# -STM32F1-4_0.net
KiCad netlist of a schematic drawn in EasyEDA Pro
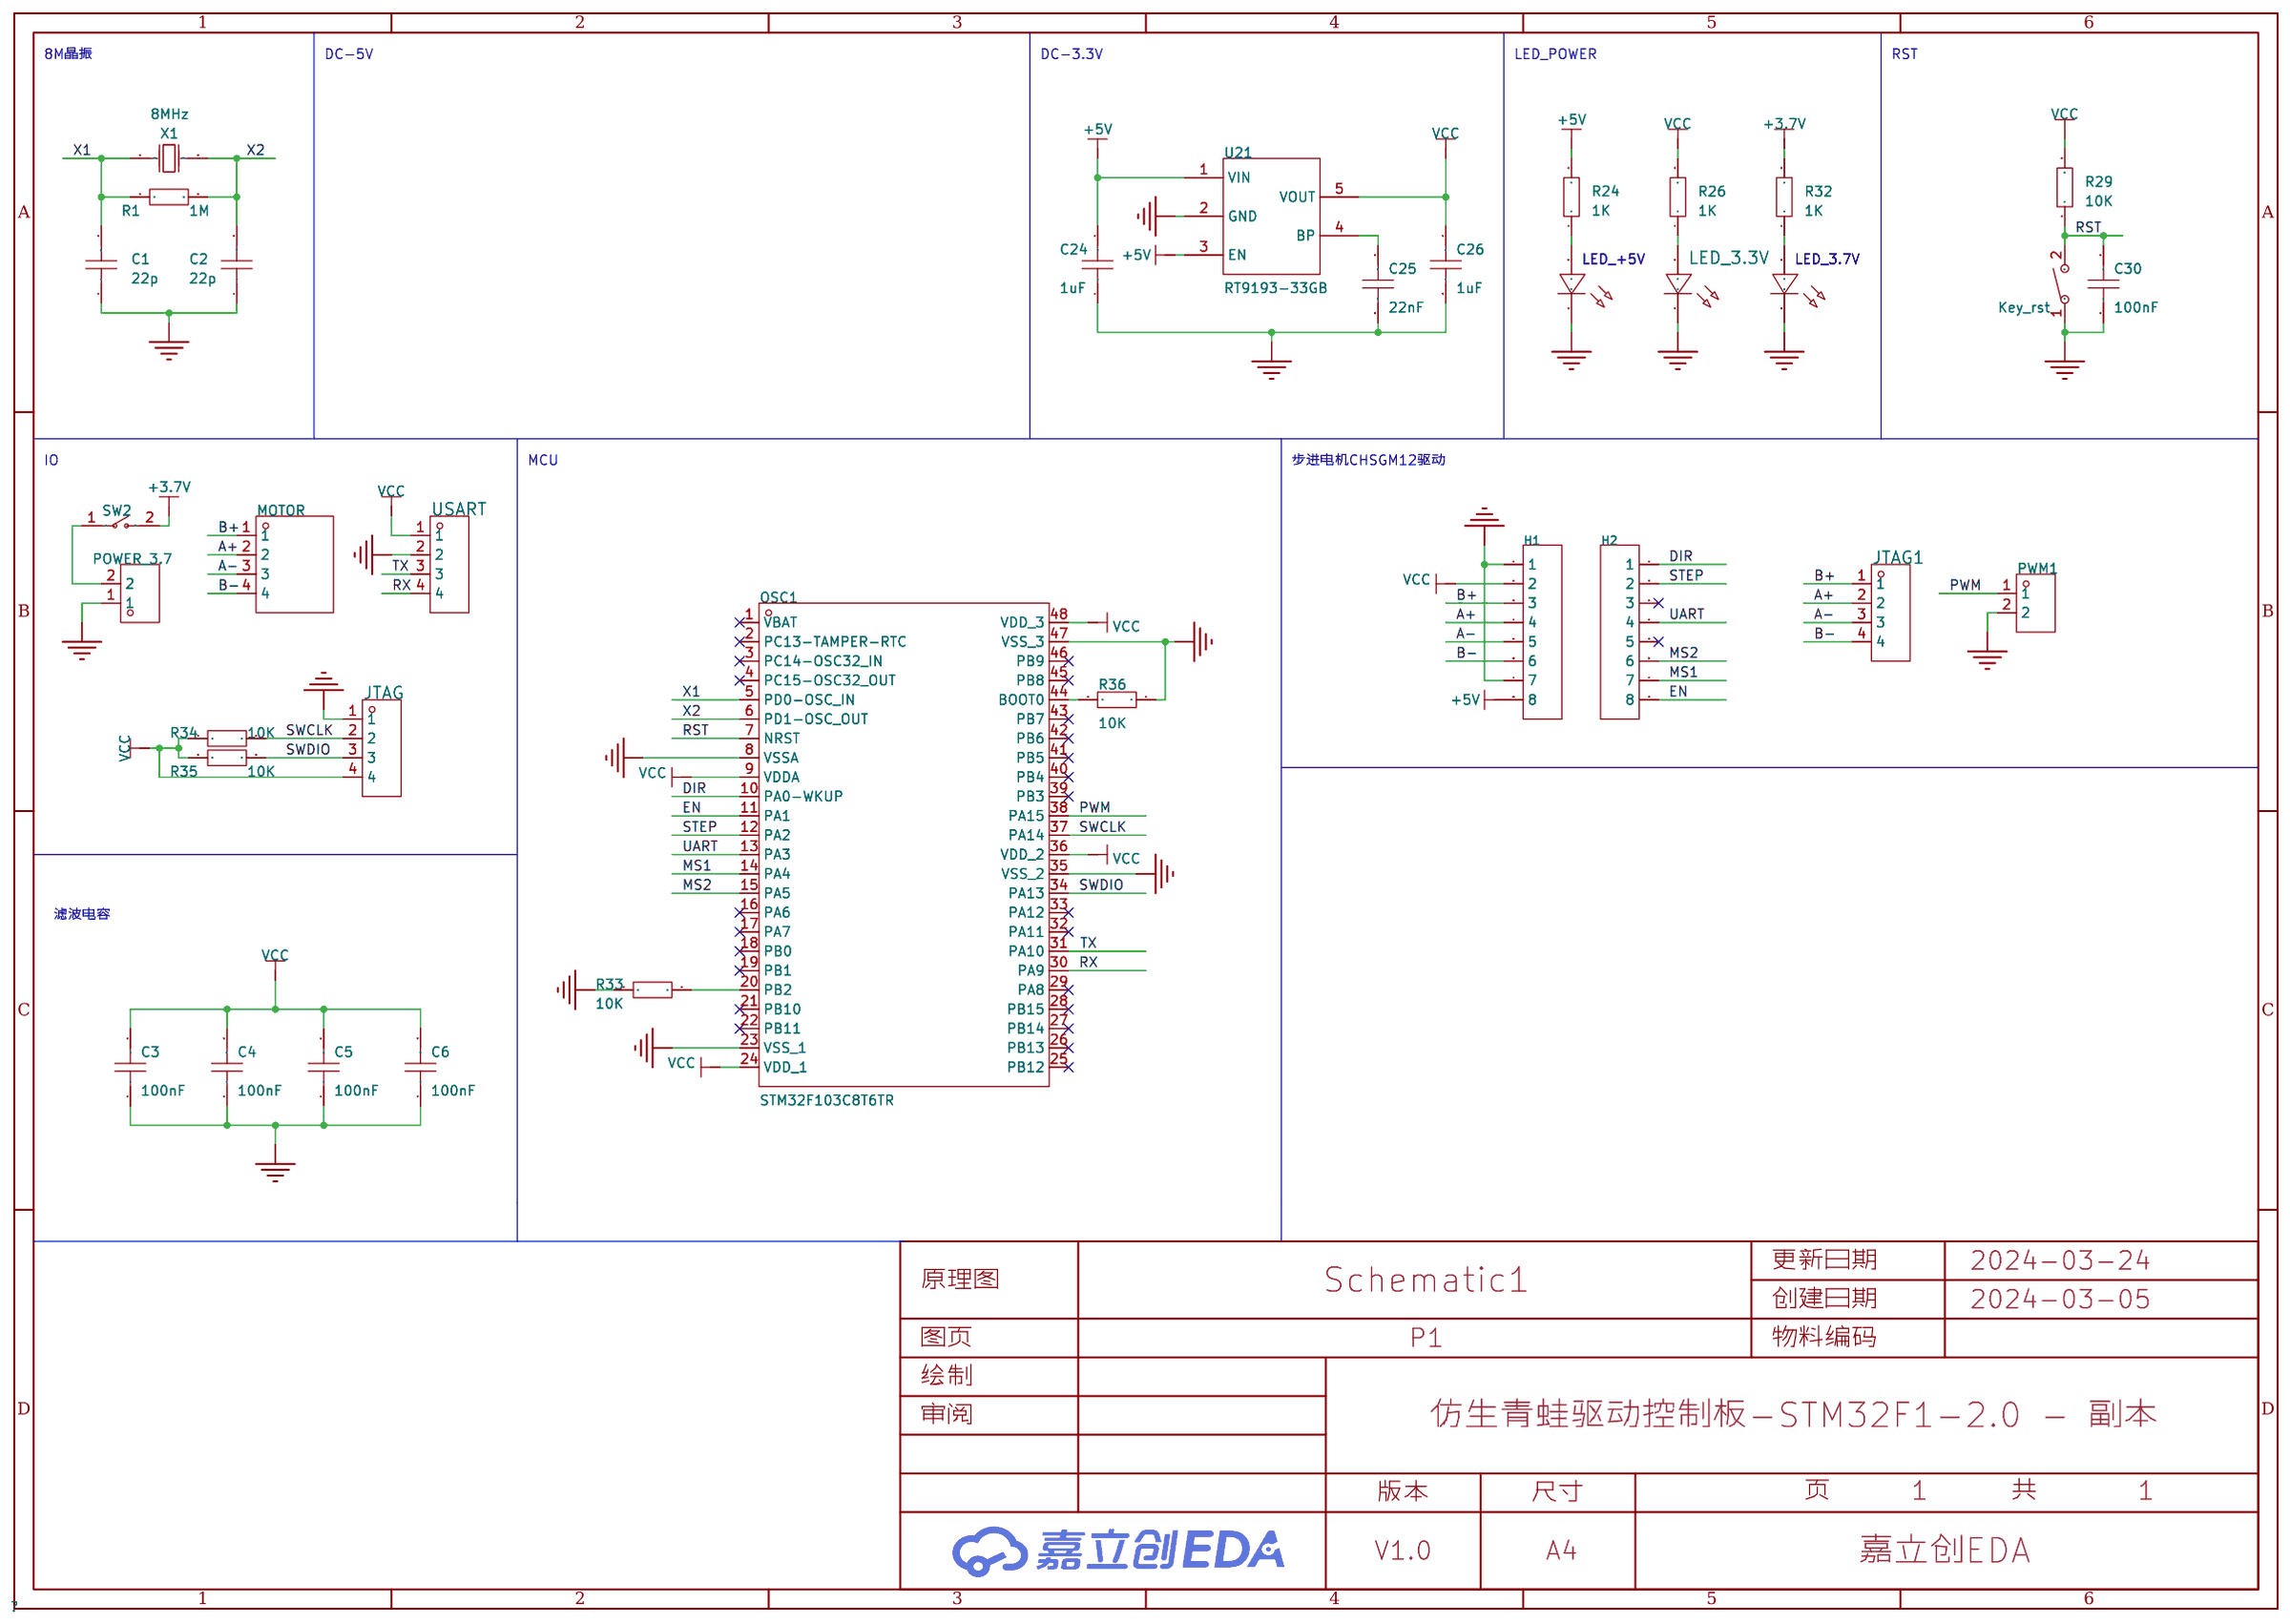
[diagram p0: schematic sheet]

(export (version "E")
  (design (tool "Eeschema 10.0.6"))
  (components
    (comp (ref "C1")
      (value "22p")
      (footprint "easyedapro:c0603")
      (libsource (lib "easyedapro") (part "CapAcitance"))
    )
    (comp (ref "C2")
      (value "22p")
      (footprint "easyedapro:c0603")
      (libsource (lib "easyedapro") (part "CapAcitance"))
    )
    (comp (ref "C3")
      (value "100nF")
      (footprint "easyedapro:c0603")
      (libsource (lib "easyedapro") (part "CapAcitance"))
    )
    (comp (ref "C4")
      (value "100nF")
      (footprint "easyedapro:c0603")
      (libsource (lib "easyedapro") (part "CapAcitance"))
    )
    (comp (ref "C5")
      (value "100nF")
      (footprint "easyedapro:c0603")
      (libsource (lib "easyedapro") (part "CapAcitance"))
    )
    (comp (ref "C6")
      (value "100nF")
      (footprint "easyedapro:c0603")
      (libsource (lib "easyedapro") (part "CapAcitance"))
    )
    (comp (ref "C24")
      (value "1uF")
      (footprint "easyedapro:c0603")
      (libsource (lib "easyedapro") (part "CapAcitance"))
    )
    (comp (ref "C25")
      (value "22nF")
      (footprint "easyedapro:c0603")
      (libsource (lib "easyedapro") (part "CapAcitance"))
    )
    (comp (ref "C26")
      (value "1uF")
      (footprint "easyedapro:c0603")
      (libsource (lib "easyedapro") (part "CapAcitance"))
    )
    (comp (ref "C30")
      (value "100nF")
      (footprint "easyedapro:c0603")
      (libsource (lib "easyedapro") (part "CapAcitance"))
    )
    (comp (ref "H1")
      (value "~")
      (footprint "easyedapro:HDR-TH_8P-P2.54-V-F-1")
      (libsource (lib "easyedapro") (part "Header-Female-2.54_1x8"))
    )
    (comp (ref "H2")
      (value "~")
      (footprint "easyedapro:HDR-TH_8P-P2.54-V-F-1")
      (libsource (lib "easyedapro") (part "Header-Female-2.54_1x8"))
    )
    (comp (ref "JTAG")
      (value "~")
      (footprint "easyedapro:HDR-TH_4P-P2.54-V-F")
      (libsource (lib "easyedapro") (part "2.54-1*4P母"))
    )
    (comp (ref "JTAG1")
      (value "~")
      (footprint "easyedapro:HDR-TH_4P-P2.54-V-F")
      (libsource (lib "easyedapro") (part "2.54-1*4P母"))
    )
    (comp (ref "Key_rst")
      (value "TS-1092S-B3D2-G")
      (footprint "easyedapro:SW-SMD_L6.1-W3.6-LS7.9")
      (description "电路结构:单刀单掷;按钮形状:矩形按钮;作用力:250gf;安装方式:立贴;开关长度:6.1mm;开关宽度:3.6mm;开关高度:2.5mm;带支架:不带;机械寿命:-;")
      (fields (field (name "Manufacturer") "Yuandi(元迪)"))
      (libsource (lib "easyedapro") (part "TS-1092S-B3D2-G"))
    )
    (comp (ref "LED_+5V")
      (value "~")
      (footprint "easyedapro:LED_0603")
      (libsource (lib "easyedapro") (part "LED_G"))
    )
    (comp (ref "LED_3.3V")
      (value "~")
      (footprint "easyedapro:LED_0402")
      (libsource (lib "easyedapro") (part "LED_R"))
    )
    (comp (ref "LED_3.7V")
      (value "~")
      (footprint "easyedapro:LED_0402")
      (libsource (lib "easyedapro") (part "LED_B"))
    )
    (comp (ref "MOTOR")
      (value "DF13-4P-1.25DSA")
      (footprint "easyedapro:CONN-TH_DF13-4P-1.25DSA")
      (description "插针结构:1x4P;间距:1.25mm;安装方式:-;参考系列:-;总PIN数:4P;排数:1;每排PIN数:4;行距:-;触头材质:黄铜;")
      (fields (field (name "Manufacturer") "HRS(广濑)"))
      (libsource (lib "easyedapro") (part "DF13-4P-1.25DSA"))
    )
    (comp (ref "OSC1")
      (value "STM32F103C8T6TR")
      (footprint "easyedapro:LQFP-48_L7.0-W7.0-P0.50-LS9.0-BL")
      (description "CPU内核:CM3;程序存储容量:64KB;RAM总容量:20KB;GPIO端口数量:37;工作电压范围:2V~3.6V;CPU最大主频:72MHz;程序存储器类型:-;")
      (fields (field (name "Manufacturer") "ST(意法半导体)"))
      (libsource (lib "easyedapro") (part "STM32F103C8T6TR"))
    )
    (comp (ref "POWER_3.7")
      (value "ZX-XH2.54-2PZZ")
      (footprint "easyedapro:CONN-TH_2P-P2.50_HX25003-2A")
      (fields (field (name "Manufacturer") "Megastar(兆星)"))
      (libsource (lib "easyedapro") (part "ZX-XH2.54-2PZZ"))
    )
    (comp (ref "PWM1")
      (value "ZX-XH2.54-2PZZ")
      (footprint "easyedapro:CONN-TH_2P-P2.50_HX25003-2A")
      (fields (field (name "Manufacturer") "Megastar(兆星)"))
      (libsource (lib "easyedapro") (part "ZX-XH2.54-2PZZ"))
    )
    (comp (ref "R1") (value "1M") (footprint "easyedapro:r0603") (libsource (lib "easyedapro") (part "电阻")))
    (comp (ref "R24") (value "1K") (footprint "easyedapro:R0805") (libsource (lib "easyedapro") (part "电阻")))
    (comp (ref "R26") (value "1K") (footprint "easyedapro:r0603") (libsource (lib "easyedapro") (part "电阻")))
    (comp (ref "R29") (value "10K") (footprint "easyedapro:r0603") (libsource (lib "easyedapro") (part "电阻")))
    (comp (ref "R32") (value "1K") (footprint "easyedapro:r0603") (libsource (lib "easyedapro") (part "电阻")))
    (comp (ref "R33") (value "10K") (footprint "easyedapro:r0603") (libsource (lib "easyedapro") (part "电阻")))
    (comp (ref "R34") (value "10K") (footprint "easyedapro:r0603") (libsource (lib "easyedapro") (part "电阻")))
    (comp (ref "R35") (value "10K") (footprint "easyedapro:r0603") (libsource (lib "easyedapro") (part "电阻")))
    (comp (ref "R36") (value "10K") (footprint "easyedapro:r0603") (libsource (lib "easyedapro") (part "电阻")))
    (comp (ref "SW2")
      (value "KCD11-2P-R")
      (footprint "easyedapro:SW-TH_2P-L15.0-W10.5-P5.00_KCD11-2P-R")
      (description "带灯:无;引脚样式:焊片;额定电流:3A;额定电压(AC):250V;额定电压(DC):-;电路结构:单刀单掷;机械寿命:1万次;")
      (fields (field (name "Manufacturer") "SHOU HAN(首韩)"))
      (libsource (lib "easyedapro") (part "KCD11-2P-R"))
    )
    (comp (ref "U21")
      (value "RT9193-33GB")
      (footprint "easyedapro:SOT-23-5_L3.0-W1.7-P0.95-LS2.8-BL")
      (description "输出类型:固定;最大输入电压:5.5V;输出电压:3.3V;最大输出电流:300mA;电源纹波抑制比(PSRR):70dB;输出极性:正极;")
      (fields (field (name "Manufacturer") "RICHTEK(立锜)"))
      (libsource (lib "easyedapro") (part "RT9193-33GB"))
    )
    (comp (ref "USART")
      (value "~")
      (footprint "easyedapro:HDR-TH_4P-P2.54-V-F")
      (libsource (lib "easyedapro") (part "2.54-1*4P母"))
    )
    (comp (ref "X1")
      (value "8MHz")
      (footprint "easyedapro:CRYSTAL-SMD_L5.0-W3.2")
      (description "晶振类型:贴片晶振;频率:8MHz;常温频差:±10ppm;外接负载电容:20pF;频率稳定度(全温):±50ppm;")
      (fields (field (name "Manufacturer Part") "X50328MSB2GI") (field (name "Manufacturer") "YXC(扬兴晶振)"))
      (libsource (lib "easyedapro") (part "X50328MSB2GI"))
    )
  )
  (nets
    (net (code "1") (name "+3.7V") (class "Default")
      (node (ref "R32") (pin "2") (pinfunction "2_2") (pintype "input"))
      (node (ref "SW2") (pin "2") (pinfunction "2_2") (pintype "unspecified"))
    )
    (net (code "2") (name "+5V") (class "Default")
      (node (ref "C24") (pin "2") (pinfunction "2_2") (pintype "input"))
      (node (ref "H1") (pin "8") (pinfunction "8_8") (pintype "input"))
      (node (ref "R24") (pin "2") (pinfunction "2_2") (pintype "input"))
      (node (ref "U21") (pin "1") (pinfunction "VIN_1") (pintype "unspecified"))
      (node (ref "U21") (pin "3") (pinfunction "EN_3") (pintype "unspecified"))
    )
    (net (code "3") (name "/A+") (class "Default")
      (node (ref "H1") (pin "4") (pinfunction "4_4") (pintype "input"))
      (node (ref "JTAG1") (pin "2") (pinfunction "2_2") (pintype "input"))
      (node (ref "MOTOR") (pin "2") (pinfunction "2_2") (pintype "unspecified"))
    )
    (net (code "4") (name "/A-") (class "Default")
      (node (ref "H1") (pin "5") (pinfunction "5_5") (pintype "input"))
      (node (ref "JTAG1") (pin "3") (pinfunction "3_3") (pintype "input"))
      (node (ref "MOTOR") (pin "3") (pinfunction "3_3") (pintype "unspecified"))
    )
    (net (code "5") (name "/B+") (class "Default")
      (node (ref "H1") (pin "3") (pinfunction "3_3") (pintype "input"))
      (node (ref "JTAG1") (pin "1") (pinfunction "1_1") (pintype "input"))
      (node (ref "MOTOR") (pin "1") (pinfunction "1_1") (pintype "unspecified"))
    )
    (net (code "6") (name "/B-") (class "Default")
      (node (ref "H1") (pin "6") (pinfunction "6_6") (pintype "input"))
      (node (ref "JTAG1") (pin "4") (pinfunction "4_4") (pintype "input"))
      (node (ref "MOTOR") (pin "4") (pinfunction "4_4") (pintype "unspecified"))
    )
    (net (code "7") (name "/DIR") (class "Default")
      (node (ref "H2") (pin "1") (pinfunction "1_1") (pintype "input"))
      (node (ref "OSC1") (pin "10") (pinfunction "PA0-WKUP_10") (pintype "unspecified"))
    )
    (net (code "8") (name "/EN") (class "Default")
      (node (ref "H2") (pin "8") (pinfunction "8_8") (pintype "input"))
      (node (ref "OSC1") (pin "11") (pinfunction "PA1_11") (pintype "unspecified"))
    )
    (net (code "9") (name "/MS1") (class "Default")
      (node (ref "H2") (pin "7") (pinfunction "7_7") (pintype "input"))
      (node (ref "OSC1") (pin "14") (pinfunction "PA4_14") (pintype "unspecified"))
    )
    (net (code "10") (name "/MS2") (class "Default")
      (node (ref "H2") (pin "6") (pinfunction "6_6") (pintype "input"))
      (node (ref "OSC1") (pin "15") (pinfunction "PA5_15") (pintype "unspecified"))
    )
    (net (code "11") (name "/PWM") (class "Default")
      (node (ref "OSC1") (pin "38") (pinfunction "PA15_38") (pintype "unspecified"))
      (node (ref "PWM1") (pin "1") (pinfunction "1_1") (pintype "unspecified"))
    )
    (net (code "12") (name "/RST") (class "Default")
      (node (ref "C30") (pin "2") (pinfunction "2_2") (pintype "input"))
      (node (ref "Key_rst") (pin "2") (pinfunction "2_2") (pintype "unspecified"))
      (node (ref "OSC1") (pin "7") (pinfunction "NRST_7") (pintype "unspecified"))
      (node (ref "R29") (pin "1") (pinfunction "1_1") (pintype "input"))
    )
    (net (code "13") (name "/RX") (class "Default")
      (node (ref "OSC1") (pin "30") (pinfunction "PA9_30") (pintype "unspecified"))
      (node (ref "USART") (pin "4") (pinfunction "4_4") (pintype "input"))
    )
    (net (code "14") (name "/STEP") (class "Default")
      (node (ref "H2") (pin "2") (pinfunction "2_2") (pintype "input"))
      (node (ref "OSC1") (pin "12") (pinfunction "PA2_12") (pintype "unspecified"))
    )
    (net (code "15") (name "/SWCLK") (class "Default")
      (node (ref "JTAG") (pin "2") (pinfunction "2_2") (pintype "input"))
      (node (ref "OSC1") (pin "37") (pinfunction "PA14_37") (pintype "unspecified"))
      (node (ref "R34") (pin "2") (pinfunction "2_2") (pintype "input"))
    )
    (net (code "16") (name "/SWDIO") (class "Default")
      (node (ref "JTAG") (pin "3") (pinfunction "3_3") (pintype "input"))
      (node (ref "OSC1") (pin "34") (pinfunction "PA13_34") (pintype "unspecified"))
      (node (ref "R35") (pin "2") (pinfunction "2_2") (pintype "input"))
    )
    (net (code "17") (name "/TX") (class "Default")
      (node (ref "OSC1") (pin "31") (pinfunction "PA10_31") (pintype "unspecified"))
      (node (ref "USART") (pin "3") (pinfunction "3_3") (pintype "input"))
    )
    (net (code "18") (name "/UART") (class "Default")
      (node (ref "H2") (pin "4") (pinfunction "4_4") (pintype "input"))
      (node (ref "OSC1") (pin "13") (pinfunction "PA3_13") (pintype "unspecified"))
    )
    (net (code "19") (name "/X1") (class "Default")
      (node (ref "C1") (pin "2") (pinfunction "2_2") (pintype "input"))
      (node (ref "OSC1") (pin "5") (pinfunction "PD0-OSC_IN_5") (pintype "unspecified"))
      (node (ref "R1") (pin "1") (pinfunction "1_1") (pintype "input"))
      (node (ref "X1") (pin "1") (pinfunction "OSC1_1") (pintype "input"))
    )
    (net (code "20") (name "/X2") (class "Default")
      (node (ref "C2") (pin "2") (pinfunction "2_2") (pintype "input"))
      (node (ref "OSC1") (pin "6") (pinfunction "PD1-OSC_OUT_6") (pintype "unspecified"))
      (node (ref "R1") (pin "2") (pinfunction "2_2") (pintype "input"))
      (node (ref "X1") (pin "2") (pinfunction "OSC2_2") (pintype "input"))
    )
    (net (code "21") (name "GND") (class "Default")
      (node (ref "C1") (pin "1") (pinfunction "1_1") (pintype "input"))
      (node (ref "C2") (pin "1") (pinfunction "1_1") (pintype "input"))
      (node (ref "C24") (pin "1") (pinfunction "1_1") (pintype "input"))
      (node (ref "C25") (pin "2") (pinfunction "2_2") (pintype "input"))
      (node (ref "C26") (pin "2") (pinfunction "2_2") (pintype "input"))
      (node (ref "C3") (pin "1") (pinfunction "1_1") (pintype "input"))
      (node (ref "C30") (pin "1") (pinfunction "1_1") (pintype "input"))
      (node (ref "C4") (pin "1") (pinfunction "1_1") (pintype "input"))
      (node (ref "C5") (pin "1") (pinfunction "1_1") (pintype "input"))
      (node (ref "C6") (pin "1") (pinfunction "1_1") (pintype "input"))
      (node (ref "H1") (pin "1") (pinfunction "1_1") (pintype "input"))
      (node (ref "H1") (pin "7") (pinfunction "7_7") (pintype "input"))
      (node (ref "JTAG") (pin "1") (pinfunction "1_1") (pintype "input"))
      (node (ref "Key_rst") (pin "1") (pinfunction "1_1") (pintype "unspecified"))
      (node (ref "LED_+5V") (pin "1") (pinfunction "C_1") (pintype "input"))
      (node (ref "LED_3.3V") (pin "1") (pinfunction "C_1") (pintype "input"))
      (node (ref "LED_3.7V") (pin "1") (pinfunction "C_1") (pintype "input"))
      (node (ref "OSC1") (pin "23") (pinfunction "VSS_1_23") (pintype "unspecified"))
      (node (ref "OSC1") (pin "35") (pinfunction "VSS_2_35") (pintype "unspecified"))
      (node (ref "OSC1") (pin "47") (pinfunction "VSS_3_47") (pintype "unspecified"))
      (node (ref "OSC1") (pin "8") (pinfunction "VSSA_8") (pintype "unspecified"))
      (node (ref "POWER_3.7") (pin "1") (pinfunction "1_1") (pintype "unspecified"))
      (node (ref "PWM1") (pin "2") (pinfunction "2_2") (pintype "unspecified"))
      (node (ref "R33") (pin "1") (pinfunction "1_1") (pintype "input"))
      (node (ref "R36") (pin "1") (pinfunction "1_1") (pintype "input"))
      (node (ref "U21") (pin "2") (pinfunction "GND_2") (pintype "unspecified"))
      (node (ref "USART") (pin "2") (pinfunction "2_2") (pintype "input"))
    )
    (net (code "22") (name "Net-(LED_+5V-A)") (class "Default")
      (node (ref "LED_+5V") (pin "2") (pinfunction "A_2") (pintype "input"))
      (node (ref "R24") (pin "1") (pinfunction "1_1") (pintype "input"))
    )
    (net (code "23") (name "Net-(LED_3.3V-A)") (class "Default")
      (node (ref "LED_3.3V") (pin "2") (pinfunction "A_2") (pintype "input"))
      (node (ref "R26") (pin "1") (pinfunction "1_1") (pintype "input"))
    )
    (net (code "24") (name "Net-(LED_3.7V-A)") (class "Default")
      (node (ref "LED_3.7V") (pin "2") (pinfunction "A_2") (pintype "input"))
      (node (ref "R32") (pin "1") (pinfunction "1_1") (pintype "input"))
    )
    (net (code "25") (name "Net-(OSC1-BOOT0)") (class "Default")
      (node (ref "OSC1") (pin "44") (pinfunction "BOOT0_44") (pintype "unspecified"))
      (node (ref "R36") (pin "2") (pinfunction "2_2") (pintype "input"))
    )
    (net (code "26") (name "Net-(OSC1-PB2)") (class "Default")
      (node (ref "OSC1") (pin "20") (pinfunction "PB2_20") (pintype "unspecified"))
      (node (ref "R33") (pin "2") (pinfunction "2_2") (pintype "input"))
    )
    (net (code "27") (name "Net-(POWER_3.7-Pad2)") (class "Default")
      (node (ref "POWER_3.7") (pin "2") (pinfunction "2_2") (pintype "unspecified"))
      (node (ref "SW2") (pin "1") (pinfunction "1_1") (pintype "unspecified"))
    )
    (net (code "28") (name "Net-(U21-BP)") (class "Default")
      (node (ref "C25") (pin "1") (pinfunction "1_1") (pintype "input"))
      (node (ref "U21") (pin "4") (pinfunction "BP_4") (pintype "unspecified"))
    )
    (net (code "29") (name "VCC") (class "Default")
      (node (ref "C26") (pin "1") (pinfunction "1_1") (pintype "input"))
      (node (ref "C3") (pin "2") (pinfunction "2_2") (pintype "input"))
      (node (ref "C4") (pin "2") (pinfunction "2_2") (pintype "input"))
      (node (ref "C5") (pin "2") (pinfunction "2_2") (pintype "input"))
      (node (ref "C6") (pin "2") (pinfunction "2_2") (pintype "input"))
      (node (ref "H1") (pin "2") (pinfunction "2_2") (pintype "input"))
      (node (ref "JTAG") (pin "4") (pinfunction "4_4") (pintype "input"))
      (node (ref "OSC1") (pin "24") (pinfunction "VDD_1_24") (pintype "unspecified"))
      (node (ref "OSC1") (pin "36") (pinfunction "VDD_2_36") (pintype "unspecified"))
      (node (ref "OSC1") (pin "48") (pinfunction "VDD_3_48") (pintype "unspecified"))
      (node (ref "OSC1") (pin "9") (pinfunction "VDDA_9") (pintype "unspecified"))
      (node (ref "R26") (pin "2") (pinfunction "2_2") (pintype "input"))
      (node (ref "R29") (pin "2") (pinfunction "2_2") (pintype "input"))
      (node (ref "R34") (pin "1") (pinfunction "1_1") (pintype "input"))
      (node (ref "R35") (pin "1") (pinfunction "1_1") (pintype "input"))
      (node (ref "U21") (pin "5") (pinfunction "VOUT_5") (pintype "unspecified"))
      (node (ref "USART") (pin "1") (pinfunction "1_1") (pintype "input"))
    )
    (net (code "30") (name "unconnected-(H2-Pad3)") (class "Default")
      (node (ref "H2") (pin "3") (pinfunction "3_3") (pintype "input+no_connect"))
    )
    (net (code "31") (name "unconnected-(H2-Pad5)") (class "Default")
      (node (ref "H2") (pin "5") (pinfunction "5_5") (pintype "input+no_connect"))
    )
    (net (code "32") (name "unconnected-(OSC1-PA6-Pad16)") (class "Default")
      (node (ref "OSC1") (pin "16") (pinfunction "PA6_16") (pintype "unspecified+no_connect"))
    )
    (net (code "33") (name "unconnected-(OSC1-PA7-Pad17)") (class "Default")
      (node (ref "OSC1") (pin "17") (pinfunction "PA7_17") (pintype "unspecified+no_connect"))
    )
    (net (code "34") (name "unconnected-(OSC1-PA8-Pad29)") (class "Default")
      (node (ref "OSC1") (pin "29") (pinfunction "PA8_29") (pintype "unspecified+no_connect"))
    )
    (net (code "35") (name "unconnected-(OSC1-PA11-Pad32)") (class "Default")
      (node (ref "OSC1") (pin "32") (pinfunction "PA11_32") (pintype "unspecified+no_connect"))
    )
    (net (code "36") (name "unconnected-(OSC1-PA12-Pad33)") (class "Default")
      (node (ref "OSC1") (pin "33") (pinfunction "PA12_33") (pintype "unspecified+no_connect"))
    )
    (net (code "37") (name "unconnected-(OSC1-PB0-Pad18)") (class "Default")
      (node (ref "OSC1") (pin "18") (pinfunction "PB0_18") (pintype "unspecified+no_connect"))
    )
    (net (code "38") (name "unconnected-(OSC1-PB1-Pad19)") (class "Default")
      (node (ref "OSC1") (pin "19") (pinfunction "PB1_19") (pintype "unspecified+no_connect"))
    )
    (net (code "39") (name "unconnected-(OSC1-PB3-Pad39)") (class "Default")
      (node (ref "OSC1") (pin "39") (pinfunction "PB3_39") (pintype "unspecified+no_connect"))
    )
    (net (code "40") (name "unconnected-(OSC1-PB4-Pad40)") (class "Default")
      (node (ref "OSC1") (pin "40") (pinfunction "PB4_40") (pintype "unspecified+no_connect"))
    )
    (net (code "41") (name "unconnected-(OSC1-PB5-Pad41)") (class "Default")
      (node (ref "OSC1") (pin "41") (pinfunction "PB5_41") (pintype "unspecified+no_connect"))
    )
    (net (code "42") (name "unconnected-(OSC1-PB6-Pad42)") (class "Default")
      (node (ref "OSC1") (pin "42") (pinfunction "PB6_42") (pintype "unspecified+no_connect"))
    )
    (net (code "43") (name "unconnected-(OSC1-PB7-Pad43)") (class "Default")
      (node (ref "OSC1") (pin "43") (pinfunction "PB7_43") (pintype "unspecified+no_connect"))
    )
    (net (code "44") (name "unconnected-(OSC1-PB8-Pad45)") (class "Default")
      (node (ref "OSC1") (pin "45") (pinfunction "PB8_45") (pintype "unspecified+no_connect"))
    )
    (net (code "45") (name "unconnected-(OSC1-PB9-Pad46)") (class "Default")
      (node (ref "OSC1") (pin "46") (pinfunction "PB9_46") (pintype "unspecified+no_connect"))
    )
    (net (code "46") (name "unconnected-(OSC1-PB10-Pad21)") (class "Default")
      (node (ref "OSC1") (pin "21") (pinfunction "PB10_21") (pintype "unspecified+no_connect"))
    )
    (net (code "47") (name "unconnected-(OSC1-PB11-Pad22)") (class "Default")
      (node (ref "OSC1") (pin "22") (pinfunction "PB11_22") (pintype "unspecified+no_connect"))
    )
    (net (code "48") (name "unconnected-(OSC1-PB12-Pad25)") (class "Default")
      (node (ref "OSC1") (pin "25") (pinfunction "PB12_25") (pintype "unspecified+no_connect"))
    )
    (net (code "49") (name "unconnected-(OSC1-PB13-Pad26)") (class "Default")
      (node (ref "OSC1") (pin "26") (pinfunction "PB13_26") (pintype "unspecified+no_connect"))
    )
    (net (code "50") (name "unconnected-(OSC1-PB14-Pad27)") (class "Default")
      (node (ref "OSC1") (pin "27") (pinfunction "PB14_27") (pintype "unspecified+no_connect"))
    )
    (net (code "51") (name "unconnected-(OSC1-PB15-Pad28)") (class "Default")
      (node (ref "OSC1") (pin "28") (pinfunction "PB15_28") (pintype "unspecified+no_connect"))
    )
    (net (code "52") (name "unconnected-(OSC1-PC13-TAMPER-RTC-Pad2)") (class "Default")
      (node (ref "OSC1") (pin "2") (pinfunction "PC13-TAMPER-RTC_2") (pintype "unspecified+no_connect"))
    )
    (net (code "53") (name "unconnected-(OSC1-PC14-OSC32_IN-Pad3)") (class "Default")
      (node (ref "OSC1") (pin "3") (pinfunction "PC14-OSC32_IN_3") (pintype "unspecified+no_connect"))
    )
    (net (code "54") (name "unconnected-(OSC1-PC15-OSC32_OUT-Pad4)") (class "Default")
      (node (ref "OSC1") (pin "4") (pinfunction "PC15-OSC32_OUT_4") (pintype "unspecified+no_connect"))
    )
    (net (code "55") (name "unconnected-(OSC1-VBAT-Pad1)") (class "Default")
      (node (ref "OSC1") (pin "1") (pinfunction "VBAT_1") (pintype "unspecified+no_connect"))
    )
  )
)
